# working.net
KiCad netlist of a schematic drawn in EAGLE
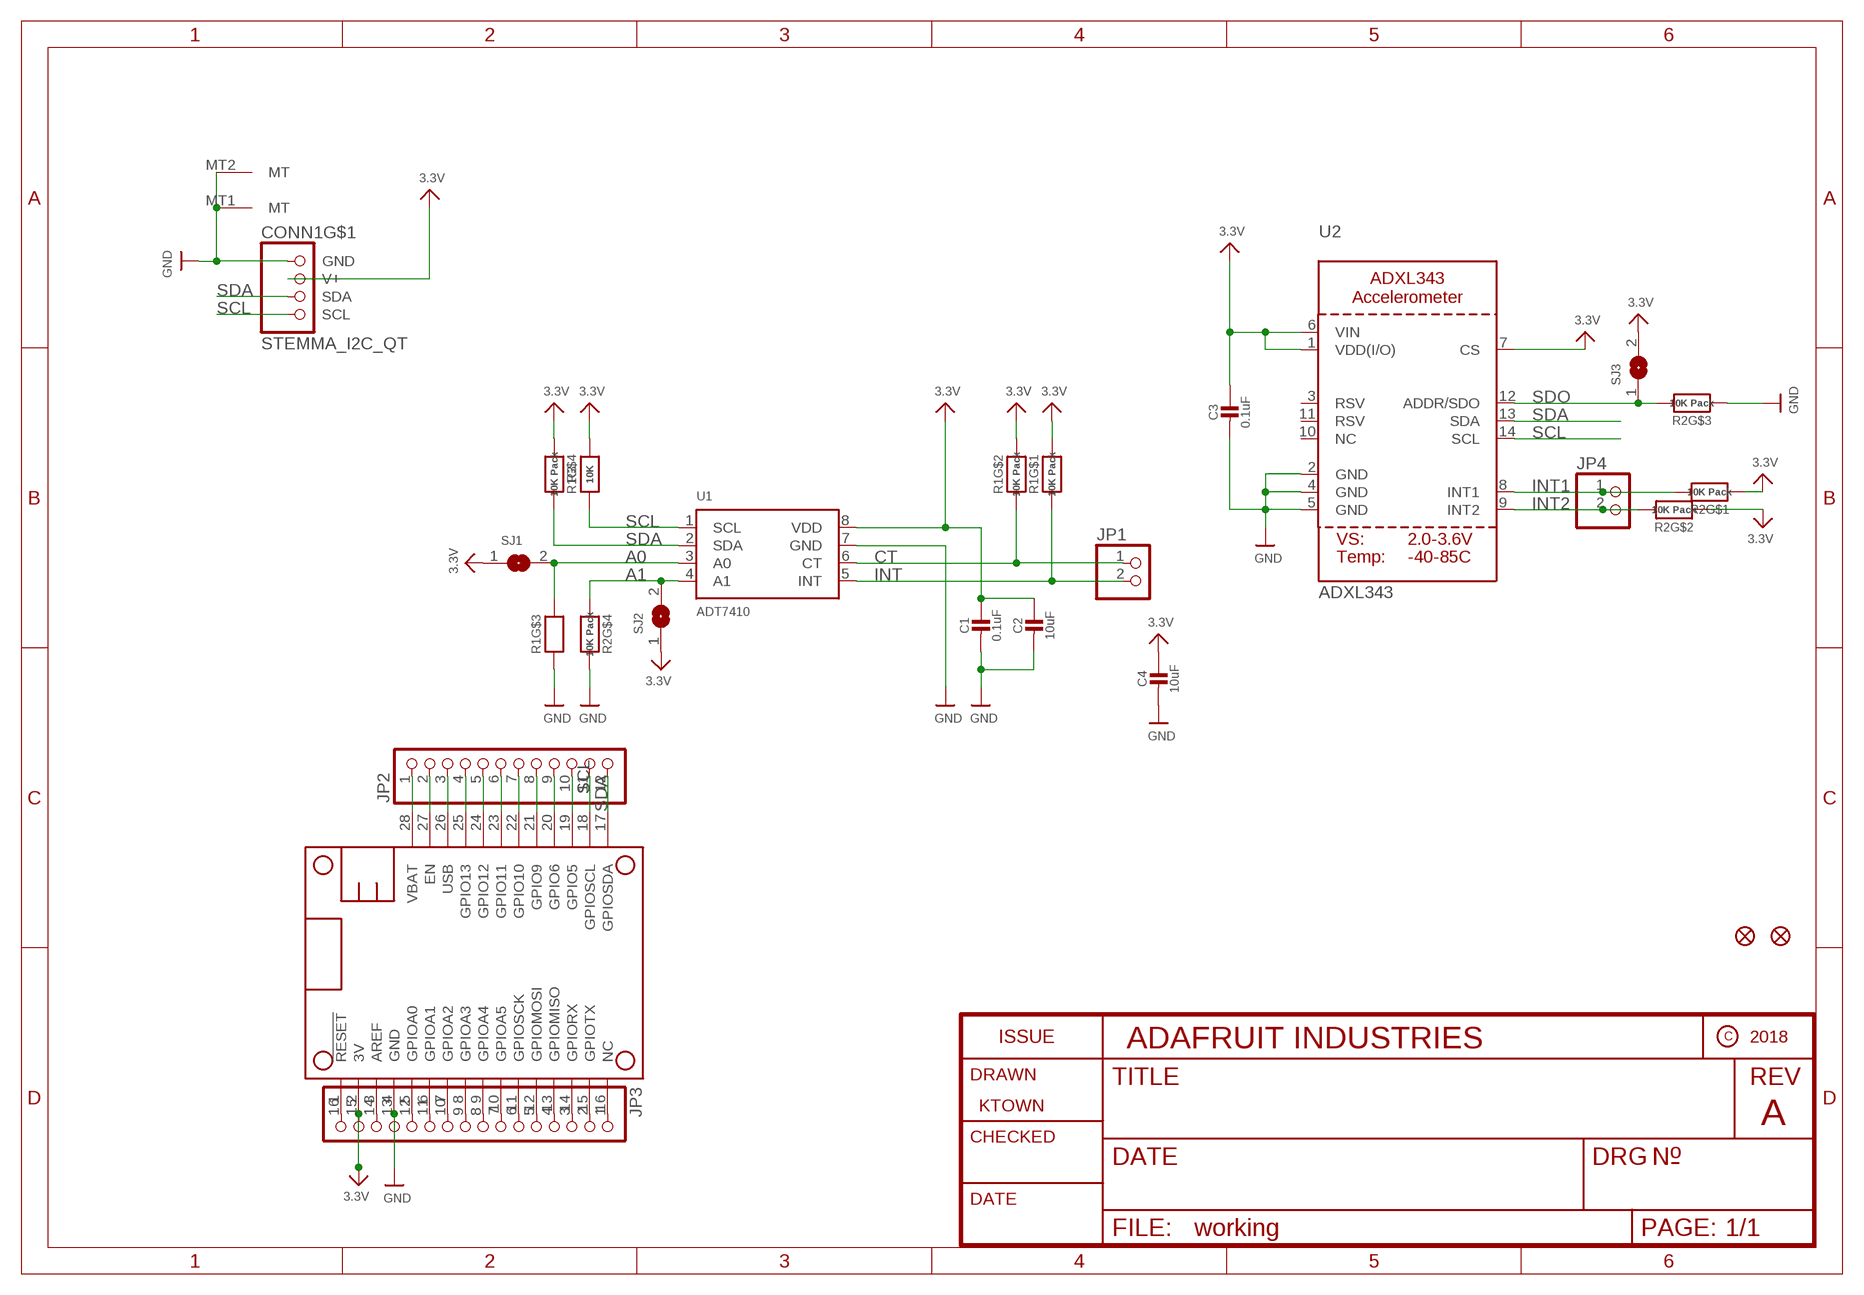
[diagram p0: schematic, sheet 1]

(export (version "E")
  (design (tool "Eeschema 10.0.6"))
  (components
    (comp (ref "C1")
      (value "0.1uF")
      (footprint "eagle-import:0603-NO")
      (libsource (lib "eagle-import") (part "CAP_CERAMIC0603_NO"))
    )
    (comp (ref "C2")
      (value "10uF")
      (footprint "eagle-import:0805-NO")
      (libsource (lib "eagle-import") (part "CAP_CERAMIC0805-NOOUTLINE"))
    )
    (comp (ref "C3")
      (value "0.1uF")
      (footprint "eagle-import:0603-NO")
      (libsource (lib "eagle-import") (part "CAP_CERAMIC0603_NO"))
    )
    (comp (ref "C4")
      (value "10uF")
      (footprint "eagle-import:0805-NO")
      (libsource (lib "eagle-import") (part "CAP_CERAMIC0805-NOOUTLINE"))
    )
    (comp (ref "CONN1")
      (value "STEMMA_I2C_QT")
      (footprint "eagle-import:JST_SH4")
      (libsource (lib "eagle-import") (part "STEMMA_I2C_QT"))
    )
    (comp (ref "FID1")
      (value "FIDUCIAL_1MM")
      (footprint "eagle-import:FIDUCIAL_1MM")
      (libsource (lib "eagle-import") (part "FIDUCIAL_1MM"))
    )
    (comp (ref "FID2")
      (value "FIDUCIAL_1MM")
      (footprint "eagle-import:FIDUCIAL_1MM")
      (libsource (lib "eagle-import") (part "FIDUCIAL_1MM"))
    )
    (comp (ref "JP1")
      (value "HEADER-1X2ROUND")
      (footprint "eagle-import:1X02_ROUND")
      (libsource (lib "eagle-import") (part "HEADER-1X2ROUND"))
    )
    (comp (ref "JP2")
      (value "HEADER-1X1276MIL")
      (footprint "eagle-import:1X12_ROUND_76MIL")
      (libsource (lib "eagle-import") (part "HEADER-1X1276MIL"))
    )
    (comp (ref "JP3")
      (value "HEADER-1X16_76MIL")
      (footprint "eagle-import:1X16_ROUND_76MIL")
      (libsource (lib "eagle-import") (part "HEADER-1X16_76MIL"))
    )
    (comp (ref "JP4")
      (value "HEADER-1X2ROUND")
      (footprint "eagle-import:1X02_ROUND")
      (libsource (lib "eagle-import") (part "HEADER-1X2ROUND"))
    )
    (comp (ref "MS1")
      (value "FEATHERWING_NODIM")
      (footprint "eagle-import:FEATHERWING_NODIM")
      (libsource (lib "eagle-import") (part "FEATHERWING_NODIM"))
    )
    (comp (ref "R1")
      (value "10K Pack")
      (footprint "eagle-import:RESPACK_4X0603")
      (libsource (lib "eagle-import") (part "RESISTOR_4PACK"))
    )
    (comp (ref "R2")
      (value "10K Pack")
      (footprint "eagle-import:RESPACK_4X0603")
      (libsource (lib "eagle-import") (part "RESISTOR_4PACK"))
    )
    (comp (ref "R3")
      (value "10K")
      (footprint "eagle-import:0603-NO")
      (libsource (lib "eagle-import") (part "RESISTOR_0603_NOOUT"))
    )
    (comp (ref "SJ1")
      (value "SOLDERJUMPER")
      (footprint "eagle-import:SOLDERJUMPER_ARROW_NOPASTE")
      (libsource (lib "eagle-import") (part "SOLDERJUMPER"))
    )
    (comp (ref "SJ2")
      (value "SOLDERJUMPER")
      (footprint "eagle-import:SOLDERJUMPER_ARROW_NOPASTE")
      (libsource (lib "eagle-import") (part "SOLDERJUMPER"))
    )
    (comp (ref "SJ3")
      (value "SOLDERJUMPER")
      (footprint "eagle-import:SOLDERJUMPER_ARROW_NOPASTE")
      (libsource (lib "eagle-import") (part "SOLDERJUMPER"))
    )
    (comp (ref "U1")
      (value "ADT7410")
      (footprint "eagle-import:SOIC8_150MIL")
      (libsource (lib "eagle-import") (part "TEMP_ADT7410"))
    )
    (comp (ref "U2")
      (value "ADXL343")
      (footprint "eagle-import:LGA14")
      (libsource (lib "eagle-import") (part "ACCEL_ADXL343"))
    )
  )
  (nets
    (net (code "1") (name "/A0") (class "Default")
      (node (ref "R1") (pin "6") (pinfunction "2_6") (pintype "passive"))
      (node (ref "SJ1") (pin "2") (pinfunction "2_2") (pintype "passive"))
      (node (ref "U1") (pin "3") (pinfunction "A0_3") (pintype "bidirectional"))
    )
    (net (code "2") (name "/A1") (class "Default")
      (node (ref "R2") (pin "4") (pinfunction "1_4") (pintype "passive"))
      (node (ref "SJ2") (pin "2") (pinfunction "2_2") (pintype "passive"))
      (node (ref "U1") (pin "4") (pinfunction "A1_4") (pintype "bidirectional"))
    )
    (net (code "3") (name "/CT") (class "Default")
      (node (ref "JP1") (pin "1") (pinfunction "1_1") (pintype "passive"))
      (node (ref "R1") (pin "2") (pinfunction "1_2") (pintype "passive"))
      (node (ref "U1") (pin "6") (pinfunction "CT_6") (pintype "bidirectional"))
    )
    (net (code "4") (name "/INT") (class "Default")
      (node (ref "JP1") (pin "2") (pinfunction "2_2") (pintype "passive"))
      (node (ref "R1") (pin "1") (pinfunction "1_1") (pintype "passive"))
      (node (ref "U1") (pin "5") (pinfunction "INT_5") (pintype "bidirectional"))
    )
    (net (code "5") (name "/INT1") (class "Default")
      (node (ref "JP4") (pin "1") (pinfunction "1_1") (pintype "passive"))
      (node (ref "R2") (pin "8") (pinfunction "2_8") (pintype "passive"))
      (node (ref "U2") (pin "8") (pinfunction "INT1_8") (pintype "bidirectional"))
    )
    (net (code "6") (name "/INT2") (class "Default")
      (node (ref "JP4") (pin "2") (pinfunction "2_2") (pintype "passive"))
      (node (ref "R2") (pin "7") (pinfunction "2_7") (pintype "passive"))
      (node (ref "U2") (pin "9") (pinfunction "INT2_9") (pintype "bidirectional"))
    )
    (net (code "7") (name "/SCL") (class "Default")
      (node (ref "CONN1") (pin "4") (pinfunction "SCL_4") (pintype "passive"))
      (node (ref "JP2") (pin "11") (pinfunction "11_11") (pintype "passive"))
      (node (ref "MS1") (pin "18") (pinfunction "GPIOSCL_18") (pintype "bidirectional"))
      (node (ref "R3") (pin "1") (pinfunction "1_1") (pintype "passive"))
      (node (ref "U1") (pin "1") (pinfunction "SCL_1") (pintype "bidirectional"))
      (node (ref "U2") (pin "14") (pinfunction "SCL_14") (pintype "bidirectional"))
    )
    (net (code "8") (name "/SDA") (class "Default")
      (node (ref "CONN1") (pin "3") (pinfunction "SDA_3") (pintype "passive"))
      (node (ref "JP2") (pin "12") (pinfunction "12_12") (pintype "passive"))
      (node (ref "MS1") (pin "17") (pinfunction "GPIOSDA_17") (pintype "bidirectional"))
      (node (ref "R1") (pin "5") (pinfunction "2_5") (pintype "passive"))
      (node (ref "U1") (pin "2") (pinfunction "SDA_2") (pintype "bidirectional"))
      (node (ref "U2") (pin "13") (pinfunction "SDA_13") (pintype "bidirectional"))
    )
    (net (code "9") (name "/SDO") (class "Default")
      (node (ref "R2") (pin "6") (pinfunction "2_6") (pintype "passive"))
      (node (ref "SJ3") (pin "1") (pinfunction "1_1") (pintype "passive"))
      (node (ref "U2") (pin "12") (pinfunction "ADDR/SDO_12") (pintype "bidirectional"))
    )
    (net (code "10") (name "3.3V") (class "Default")
      (node (ref "C1") (pin "1") (pinfunction "1_1") (pintype "passive"))
      (node (ref "C2") (pin "1") (pinfunction "1_1") (pintype "passive"))
      (node (ref "C3") (pin "1") (pinfunction "1_1") (pintype "passive"))
      (node (ref "C4") (pin "1") (pinfunction "1_1") (pintype "passive"))
      (node (ref "CONN1") (pin "2") (pinfunction "V+_2") (pintype "passive"))
      (node (ref "JP3") (pin "15") (pinfunction "15_15") (pintype "passive"))
      (node (ref "MS1") (pin "2") (pinfunction "3V_2") (pintype "power_in"))
      (node (ref "R1") (pin "4") (pinfunction "1_4") (pintype "passive"))
      (node (ref "R1") (pin "7") (pinfunction "2_7") (pintype "passive"))
      (node (ref "R1") (pin "8") (pinfunction "2_8") (pintype "passive"))
      (node (ref "R2") (pin "1") (pinfunction "1_1") (pintype "passive"))
      (node (ref "R2") (pin "2") (pinfunction "1_2") (pintype "passive"))
      (node (ref "R3") (pin "2") (pinfunction "2_2") (pintype "passive"))
      (node (ref "SJ1") (pin "1") (pinfunction "1_1") (pintype "passive"))
      (node (ref "SJ2") (pin "1") (pinfunction "1_1") (pintype "passive"))
      (node (ref "SJ3") (pin "2") (pinfunction "2_2") (pintype "passive"))
      (node (ref "U1") (pin "8") (pinfunction "VDD_8") (pintype "power_in"))
      (node (ref "U2") (pin "1") (pinfunction "VDD(I/O)_1") (pintype "bidirectional"))
      (node (ref "U2") (pin "6") (pinfunction "VIN_6") (pintype "bidirectional"))
      (node (ref "U2") (pin "7") (pinfunction "CS_7") (pintype "bidirectional"))
    )
    (net (code "11") (name "GND") (class "Default")
      (node (ref "C1") (pin "2") (pinfunction "2_2") (pintype "passive"))
      (node (ref "C2") (pin "2") (pinfunction "2_2") (pintype "passive"))
      (node (ref "C3") (pin "2") (pinfunction "2_2") (pintype "passive"))
      (node (ref "C4") (pin "2") (pinfunction "2_2") (pintype "passive"))
      (node (ref "CONN1") (pin "1") (pinfunction "GND_1") (pintype "passive"))
      (node (ref "CONN1") (pin "MT1") (pinfunction "MT_MT1") (pintype "bidirectional"))
      (node (ref "CONN1") (pin "MT2") (pinfunction "MT_MT2") (pintype "bidirectional"))
      (node (ref "JP3") (pin "13") (pinfunction "13_13") (pintype "passive"))
      (node (ref "MS1") (pin "4") (pinfunction "GND_4") (pintype "power_in"))
      (node (ref "R1") (pin "3") (pinfunction "1_3") (pintype "passive"))
      (node (ref "R2") (pin "3") (pinfunction "1_3") (pintype "passive"))
      (node (ref "R2") (pin "5") (pinfunction "2_5") (pintype "passive"))
      (node (ref "U1") (pin "7") (pinfunction "GND_7") (pintype "power_in"))
      (node (ref "U2") (pin "2") (pinfunction "GND_2") (pintype "bidirectional"))
      (node (ref "U2") (pin "4") (pinfunction "GND_4") (pintype "bidirectional"))
      (node (ref "U2") (pin "5") (pinfunction "GND_5") (pintype "bidirectional"))
    )
    (net (code "12") (name "Net-(MS1-AREF)") (class "Default")
      (node (ref "JP3") (pin "14") (pinfunction "14_14") (pintype "passive"))
      (node (ref "MS1") (pin "3") (pinfunction "AREF_3") (pintype "passive"))
    )
    (net (code "13") (name "Net-(MS1-EN)") (class "Default")
      (node (ref "JP2") (pin "2") (pinfunction "2_2") (pintype "passive"))
      (node (ref "MS1") (pin "27") (pinfunction "EN_27") (pintype "passive"))
    )
    (net (code "14") (name "Net-(MS1-GPIO5)") (class "Default")
      (node (ref "JP2") (pin "10") (pinfunction "10_10") (pintype "passive"))
      (node (ref "MS1") (pin "19") (pinfunction "GPIO5_19") (pintype "bidirectional"))
    )
    (net (code "15") (name "Net-(MS1-GPIO6)") (class "Default")
      (node (ref "JP2") (pin "9") (pinfunction "9_9") (pintype "passive"))
      (node (ref "MS1") (pin "20") (pinfunction "GPIO6_20") (pintype "bidirectional"))
    )
    (net (code "16") (name "Net-(MS1-GPIO9)") (class "Default")
      (node (ref "JP2") (pin "8") (pinfunction "8_8") (pintype "passive"))
      (node (ref "MS1") (pin "21") (pinfunction "GPIO9_21") (pintype "bidirectional"))
    )
    (net (code "17") (name "Net-(MS1-GPIO10)") (class "Default")
      (node (ref "JP2") (pin "7") (pinfunction "7_7") (pintype "passive"))
      (node (ref "MS1") (pin "22") (pinfunction "GPIO10_22") (pintype "bidirectional"))
    )
    (net (code "18") (name "Net-(MS1-GPIO11)") (class "Default")
      (node (ref "JP2") (pin "6") (pinfunction "6_6") (pintype "passive"))
      (node (ref "MS1") (pin "23") (pinfunction "GPIO11_23") (pintype "bidirectional"))
    )
    (net (code "19") (name "Net-(MS1-GPIO12)") (class "Default")
      (node (ref "JP2") (pin "5") (pinfunction "5_5") (pintype "passive"))
      (node (ref "MS1") (pin "24") (pinfunction "GPIO12_24") (pintype "bidirectional"))
    )
    (net (code "20") (name "Net-(MS1-GPIO13)") (class "Default")
      (node (ref "JP2") (pin "4") (pinfunction "4_4") (pintype "passive"))
      (node (ref "MS1") (pin "25") (pinfunction "GPIO13_25") (pintype "bidirectional"))
    )
    (net (code "21") (name "Net-(MS1-GPIOA0)") (class "Default")
      (node (ref "JP3") (pin "12") (pinfunction "12_12") (pintype "passive"))
      (node (ref "MS1") (pin "5") (pinfunction "GPIOA0_5") (pintype "bidirectional"))
    )
    (net (code "22") (name "Net-(MS1-GPIOA1)") (class "Default")
      (node (ref "JP3") (pin "11") (pinfunction "11_11") (pintype "passive"))
      (node (ref "MS1") (pin "6") (pinfunction "GPIOA1_6") (pintype "bidirectional"))
    )
    (net (code "23") (name "Net-(MS1-GPIOA2)") (class "Default")
      (node (ref "JP3") (pin "10") (pinfunction "10_10") (pintype "passive"))
      (node (ref "MS1") (pin "7") (pinfunction "GPIOA2_7") (pintype "bidirectional"))
    )
    (net (code "24") (name "Net-(MS1-GPIOA3)") (class "Default")
      (node (ref "JP3") (pin "9") (pinfunction "9_9") (pintype "passive"))
      (node (ref "MS1") (pin "8") (pinfunction "GPIOA3_8") (pintype "bidirectional"))
    )
    (net (code "25") (name "Net-(MS1-GPIOA4)") (class "Default")
      (node (ref "JP3") (pin "8") (pinfunction "8_8") (pintype "passive"))
      (node (ref "MS1") (pin "9") (pinfunction "GPIOA4_9") (pintype "bidirectional"))
    )
    (net (code "26") (name "Net-(MS1-GPIOA5)") (class "Default")
      (node (ref "JP3") (pin "7") (pinfunction "7_7") (pintype "passive"))
      (node (ref "MS1") (pin "10") (pinfunction "GPIOA5_10") (pintype "bidirectional"))
    )
    (net (code "27") (name "Net-(MS1-GPIOMISO)") (class "Default")
      (node (ref "JP3") (pin "4") (pinfunction "4_4") (pintype "passive"))
      (node (ref "MS1") (pin "13") (pinfunction "GPIOMISO_13") (pintype "bidirectional"))
    )
    (net (code "28") (name "Net-(MS1-GPIOMOSI)") (class "Default")
      (node (ref "JP3") (pin "5") (pinfunction "5_5") (pintype "passive"))
      (node (ref "MS1") (pin "12") (pinfunction "GPIOMOSI_12") (pintype "bidirectional"))
    )
    (net (code "29") (name "Net-(MS1-GPIORX)") (class "Default")
      (node (ref "JP3") (pin "3") (pinfunction "3_3") (pintype "passive"))
      (node (ref "MS1") (pin "14") (pinfunction "GPIORX_14") (pintype "bidirectional"))
    )
    (net (code "30") (name "Net-(MS1-GPIOSCK)") (class "Default")
      (node (ref "JP3") (pin "6") (pinfunction "6_6") (pintype "passive"))
      (node (ref "MS1") (pin "11") (pinfunction "GPIOSCK_11") (pintype "bidirectional"))
    )
    (net (code "31") (name "Net-(MS1-GPIOTX)") (class "Default")
      (node (ref "JP3") (pin "2") (pinfunction "2_2") (pintype "passive"))
      (node (ref "MS1") (pin "15") (pinfunction "GPIOTX_15") (pintype "bidirectional"))
    )
    (net (code "32") (name "Net-(MS1-NC)") (class "Default")
      (node (ref "JP3") (pin "1") (pinfunction "1_1") (pintype "passive"))
      (node (ref "MS1") (pin "16") (pinfunction "NC_16") (pintype "passive"))
    )
    (net (code "33") (name "Net-(MS1-USB)") (class "Default")
      (node (ref "JP2") (pin "3") (pinfunction "3_3") (pintype "passive"))
      (node (ref "MS1") (pin "26") (pinfunction "USB_26") (pintype "power_in"))
    )
    (net (code "34") (name "Net-(MS1-VBAT)") (class "Default")
      (node (ref "JP2") (pin "1") (pinfunction "1_1") (pintype "passive"))
      (node (ref "MS1") (pin "28") (pinfunction "VBAT_28") (pintype "power_in"))
    )
    (net (code "35") (name "Net-(MS1-~{RESET})") (class "Default")
      (node (ref "JP3") (pin "16") (pinfunction "16_16") (pintype "passive"))
      (node (ref "MS1") (pin "1") (pinfunction "~{RESET}_1") (pintype "input"))
    )
    (net (code "36") (name "unconnected-(U2-NC-Pad10)") (class "Default")
      (node (ref "U2") (pin "10") (pinfunction "NC_10") (pintype "bidirectional"))
    )
    (net (code "37") (name "unconnected-(U2-RSV-Pad3)") (class "Default")
      (node (ref "U2") (pin "3") (pinfunction "RSV_3") (pintype "bidirectional"))
    )
    (net (code "38") (name "unconnected-(U2-RSV-Pad11)") (class "Default")
      (node (ref "U2") (pin "11") (pinfunction "RSV_11") (pintype "bidirectional"))
    )
  )
)
